# BATT_FLEX11.net
KiCad netlist of a schematic drawn in EAGLE
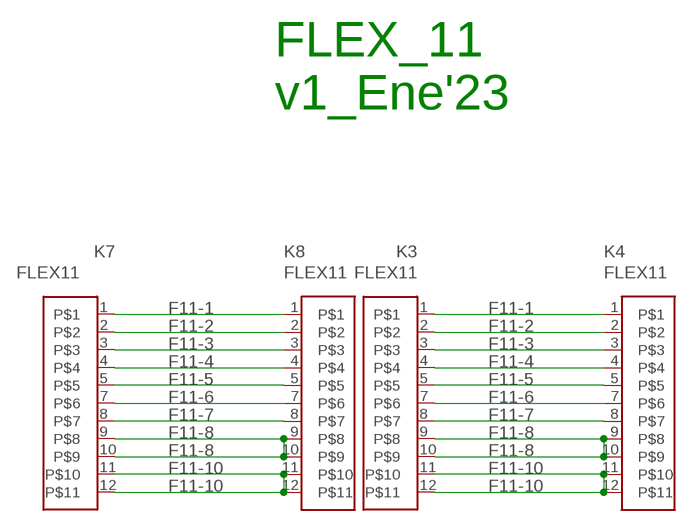
[diagram p0: schematic, sheet 1]

(export (version "E")
  (design (tool "Eeschema 10.0.6"))
  (components
    (comp (ref "K3")
      (value "FLEX11")
      (footprint "eagle-import:FLEX11")
      (libsource (lib "eagle-import") (part "FLEX11"))
    )
    (comp (ref "K4")
      (value "FLEX11")
      (footprint "eagle-import:FLEX11")
      (libsource (lib "eagle-import") (part "FLEX11"))
    )
    (comp (ref "K7")
      (value "FLEX11")
      (footprint "eagle-import:FLEX11")
      (libsource (lib "eagle-import") (part "FLEX11"))
    )
    (comp (ref "K8")
      (value "FLEX11")
      (footprint "eagle-import:FLEX11")
      (libsource (lib "eagle-import") (part "FLEX11"))
    )
  )
  (nets
    (net (code "1") (name "/F11-1") (class "Default")
      (node (ref "K3") (pin "1") (pinfunction "P$1_1") (pintype "bidirectional"))
      (node (ref "K4") (pin "1") (pinfunction "P$1_1") (pintype "bidirectional"))
      (node (ref "K7") (pin "1") (pinfunction "P$1_1") (pintype "bidirectional"))
      (node (ref "K8") (pin "1") (pinfunction "P$1_1") (pintype "bidirectional"))
    )
    (net (code "2") (name "/F11-2") (class "Default")
      (node (ref "K3") (pin "2") (pinfunction "P$2_2") (pintype "bidirectional"))
      (node (ref "K4") (pin "2") (pinfunction "P$2_2") (pintype "bidirectional"))
      (node (ref "K7") (pin "2") (pinfunction "P$2_2") (pintype "bidirectional"))
      (node (ref "K8") (pin "2") (pinfunction "P$2_2") (pintype "bidirectional"))
    )
    (net (code "3") (name "/F11-3") (class "Default")
      (node (ref "K3") (pin "3") (pinfunction "P$3_3") (pintype "bidirectional"))
      (node (ref "K4") (pin "3") (pinfunction "P$3_3") (pintype "bidirectional"))
      (node (ref "K7") (pin "3") (pinfunction "P$3_3") (pintype "bidirectional"))
      (node (ref "K8") (pin "3") (pinfunction "P$3_3") (pintype "bidirectional"))
    )
    (net (code "4") (name "/F11-4") (class "Default")
      (node (ref "K3") (pin "4") (pinfunction "P$4_4") (pintype "bidirectional"))
      (node (ref "K4") (pin "4") (pinfunction "P$4_4") (pintype "bidirectional"))
      (node (ref "K7") (pin "4") (pinfunction "P$4_4") (pintype "bidirectional"))
      (node (ref "K8") (pin "4") (pinfunction "P$4_4") (pintype "bidirectional"))
    )
    (net (code "5") (name "/F11-5") (class "Default")
      (node (ref "K3") (pin "5") (pinfunction "P$5_5") (pintype "bidirectional"))
      (node (ref "K4") (pin "5") (pinfunction "P$5_5") (pintype "bidirectional"))
      (node (ref "K7") (pin "5") (pinfunction "P$5_5") (pintype "bidirectional"))
      (node (ref "K8") (pin "5") (pinfunction "P$5_5") (pintype "bidirectional"))
    )
    (net (code "6") (name "/F11-6") (class "Default")
      (node (ref "K3") (pin "7") (pinfunction "P$6_7") (pintype "bidirectional"))
      (node (ref "K4") (pin "7") (pinfunction "P$6_7") (pintype "bidirectional"))
      (node (ref "K7") (pin "7") (pinfunction "P$6_7") (pintype "bidirectional"))
      (node (ref "K8") (pin "7") (pinfunction "P$6_7") (pintype "bidirectional"))
    )
    (net (code "7") (name "/F11-7") (class "Default")
      (node (ref "K3") (pin "8") (pinfunction "P$7_8") (pintype "bidirectional"))
      (node (ref "K4") (pin "8") (pinfunction "P$7_8") (pintype "bidirectional"))
      (node (ref "K7") (pin "8") (pinfunction "P$7_8") (pintype "bidirectional"))
      (node (ref "K8") (pin "8") (pinfunction "P$7_8") (pintype "bidirectional"))
    )
    (net (code "8") (name "/F11-8") (class "Default")
      (node (ref "K3") (pin "10") (pinfunction "P$9_10") (pintype "bidirectional"))
      (node (ref "K3") (pin "9") (pinfunction "P$8_9") (pintype "bidirectional"))
      (node (ref "K4") (pin "10") (pinfunction "P$9_10") (pintype "bidirectional"))
      (node (ref "K4") (pin "9") (pinfunction "P$8_9") (pintype "bidirectional"))
      (node (ref "K7") (pin "10") (pinfunction "P$9_10") (pintype "bidirectional"))
      (node (ref "K7") (pin "9") (pinfunction "P$8_9") (pintype "bidirectional"))
      (node (ref "K8") (pin "10") (pinfunction "P$9_10") (pintype "bidirectional"))
      (node (ref "K8") (pin "9") (pinfunction "P$8_9") (pintype "bidirectional"))
    )
    (net (code "9") (name "/F11-10") (class "Default")
      (node (ref "K3") (pin "11") (pinfunction "P$10_11") (pintype "bidirectional"))
      (node (ref "K3") (pin "12") (pinfunction "P$11_12") (pintype "bidirectional"))
      (node (ref "K4") (pin "11") (pinfunction "P$10_11") (pintype "bidirectional"))
      (node (ref "K4") (pin "12") (pinfunction "P$11_12") (pintype "bidirectional"))
      (node (ref "K7") (pin "11") (pinfunction "P$10_11") (pintype "bidirectional"))
      (node (ref "K7") (pin "12") (pinfunction "P$11_12") (pintype "bidirectional"))
      (node (ref "K8") (pin "11") (pinfunction "P$10_11") (pintype "bidirectional"))
      (node (ref "K8") (pin "12") (pinfunction "P$11_12") (pintype "bidirectional"))
    )
  )
)
